# Full_PCB.net
KiCad netlist of a schematic drawn in EAGLE
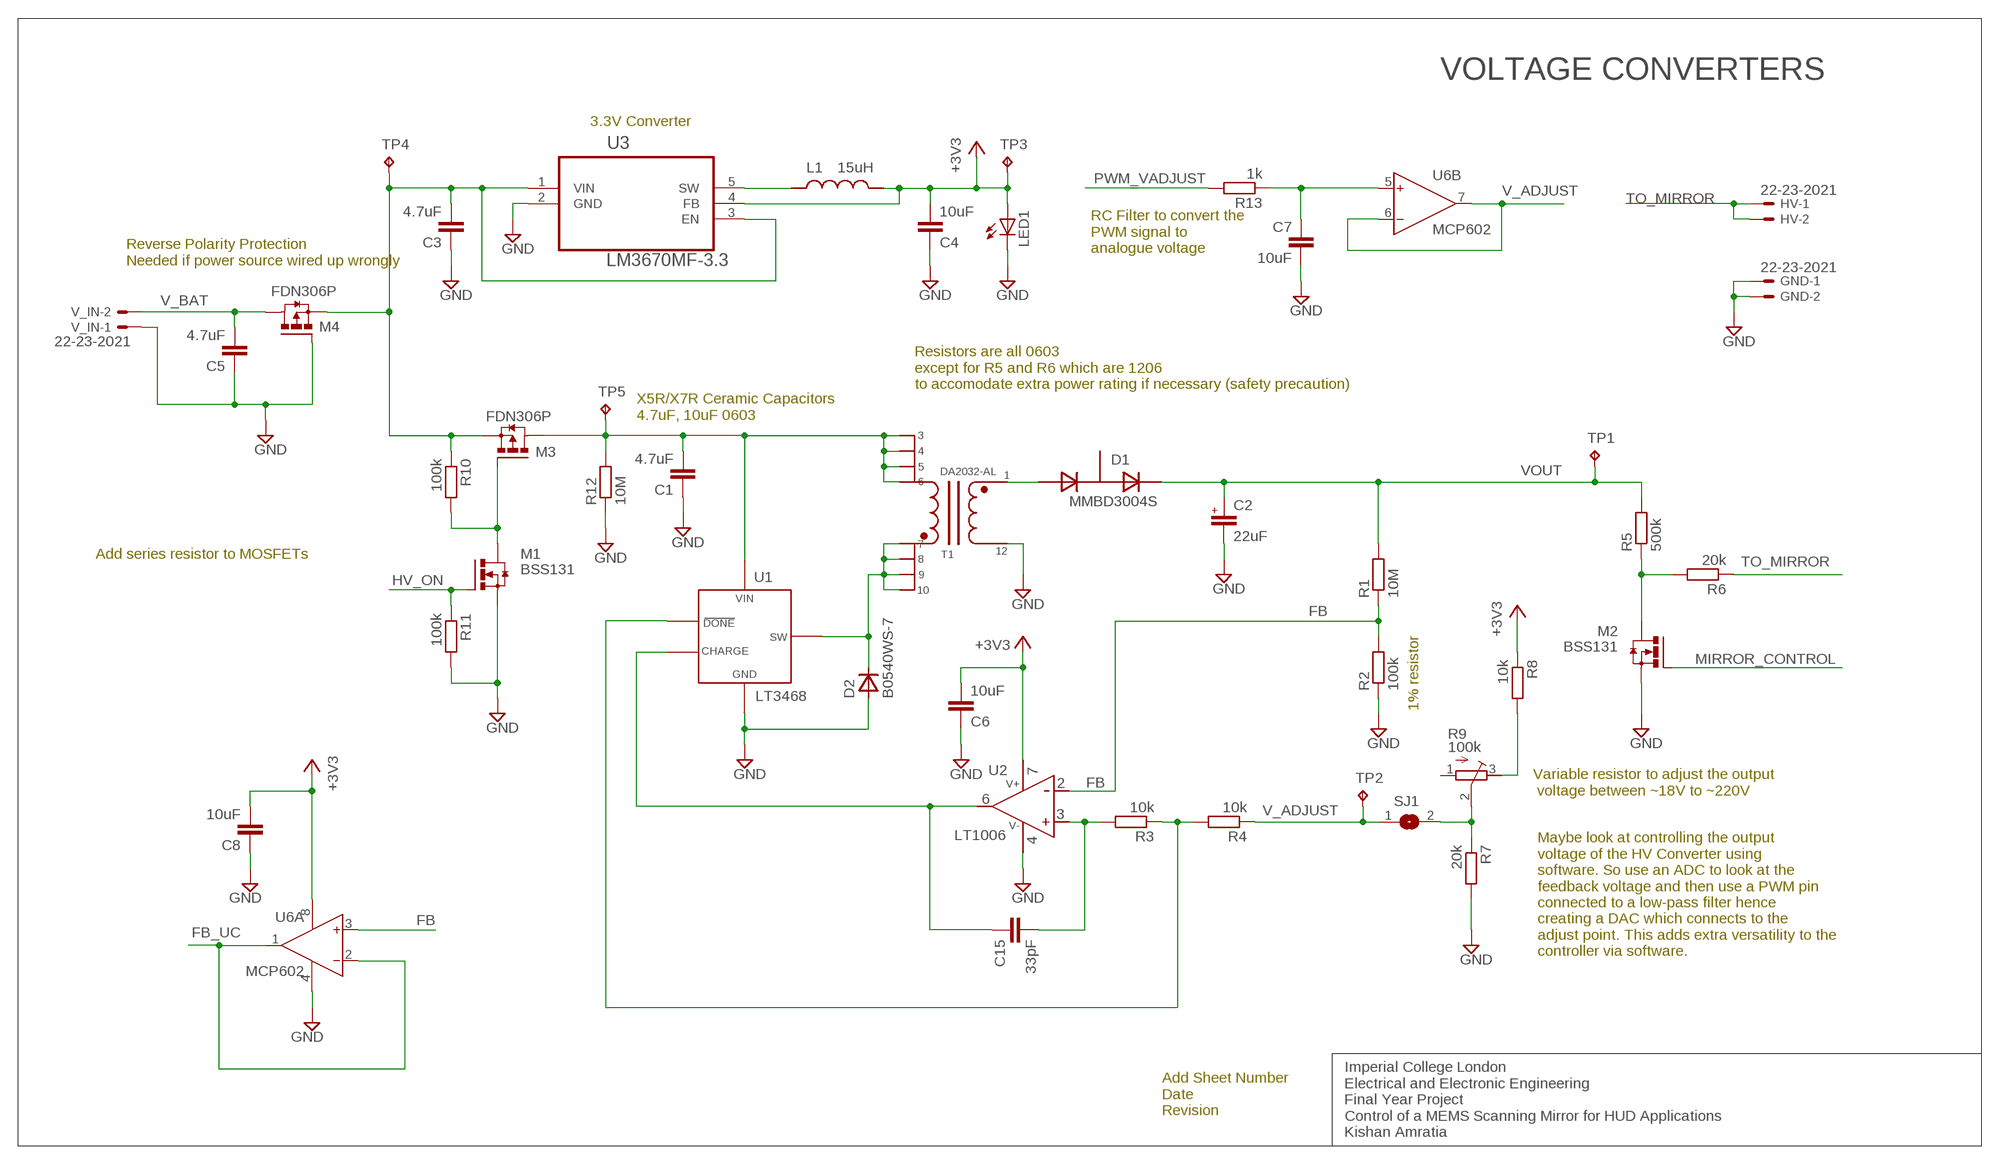
[diagram p0: schematic, sheet 1]
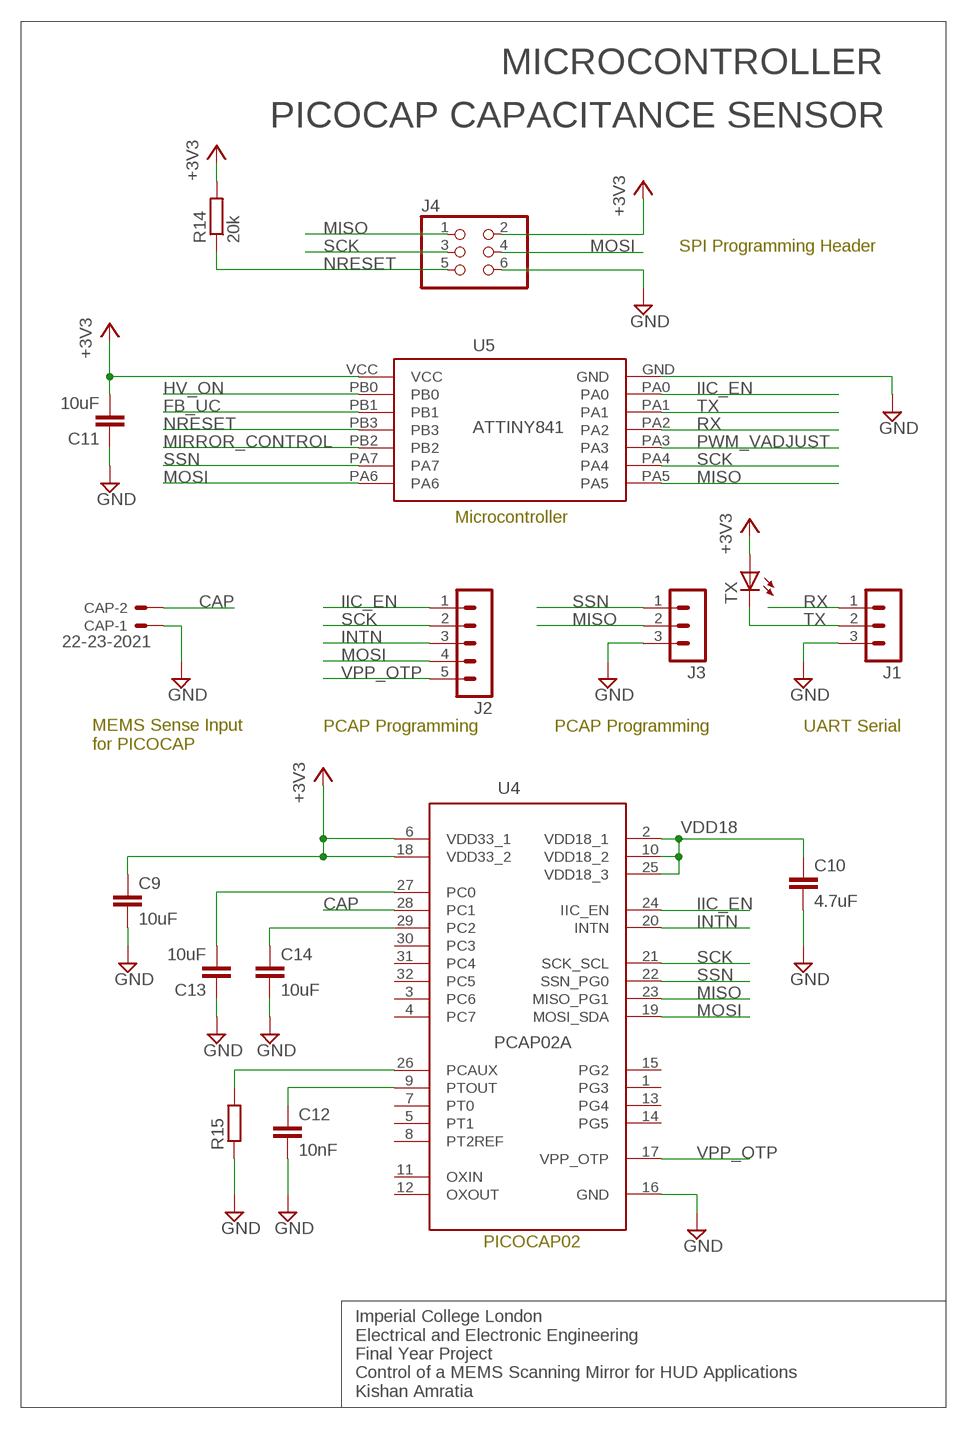
[diagram p1: schematic, sheet 2]

(export (version "E")
  (design (tool "Eeschema 10.0.6"))
  (components
    (comp (ref "C1")
      (value "4.7uF")
      (footprint "eagle-import:C0603K")
      (libsource (lib "eagle-import") (part "C-EUC0603K"))
    )
    (comp (ref "C2")
      (value "22uF")
      (footprint "eagle-import:5MM-RADIAL-LEAD")
      (libsource (lib "eagle-import") (part "EEUEE2E220"))
    )
    (comp (ref "C3")
      (value "4.7uF")
      (footprint "eagle-import:C0603K")
      (libsource (lib "eagle-import") (part "C-EUC0603K"))
    )
    (comp (ref "C4")
      (value "10uF")
      (footprint "eagle-import:C0603")
      (libsource (lib "eagle-import") (part "C-EUC0603"))
    )
    (comp (ref "C5")
      (value "4.7uF")
      (footprint "eagle-import:C0603K")
      (libsource (lib "eagle-import") (part "C-EUC0603K"))
    )
    (comp (ref "C6")
      (value "10uF")
      (footprint "eagle-import:C0603")
      (libsource (lib "eagle-import") (part "C-EUC0603"))
    )
    (comp (ref "C7")
      (value "10uF")
      (footprint "eagle-import:C0603")
      (libsource (lib "eagle-import") (part "C-EUC0603"))
    )
    (comp (ref "C8")
      (value "10uF")
      (footprint "eagle-import:C0603")
      (libsource (lib "eagle-import") (part "C-EUC0603"))
    )
    (comp (ref "C15")
      (value "33pF")
      (footprint "eagle-import:C0603")
      (libsource (lib "eagle-import") (part "C-EUC0603"))
    )
    (comp (ref "D1")
      (value "MMBD3004S")
      (footprint "eagle-import:SOT-23")
      (libsource (lib "eagle-import") (part "MMBD3004S"))
    )
    (comp (ref "D2")
      (value "B0540WS-7")
      (footprint "eagle-import:SOD-323")
      (libsource (lib "eagle-import") (part "B0540WS-7"))
    )
    (comp (ref "GND")
      (value "22-23-2021")
      (footprint "eagle-import:22-23-2021")
      (fields (field (name "MF") "MOLEX"))
      (libsource (lib "eagle-import") (part "22-23-2021"))
    )
    (comp (ref "HV")
      (value "22-23-2021")
      (footprint "eagle-import:22-23-2021")
      (fields (field (name "MF") "MOLEX"))
      (libsource (lib "eagle-import") (part "22-23-2021"))
    )
    (comp (ref "L1")
      (value "15uH")
      (footprint "eagle-import:IFSC1515AHER150M01")
      (libsource (lib "eagle-import") (part "IFSC1515AHER150M01"))
    )
    (comp (ref "LED1")
      (value "LEDCHIPLED_0603")
      (footprint "eagle-import:CHIPLED_0603")
      (libsource (lib "eagle-import") (part "LEDCHIPLED_0603"))
    )
    (comp (ref "M1")
      (value "BSS131")
      (footprint "eagle-import:SOT-23")
      (libsource (lib "eagle-import") (part "BSS131"))
    )
    (comp (ref "M2")
      (value "BSS131")
      (footprint "eagle-import:SOT-23")
      (libsource (lib "eagle-import") (part "BSS131"))
    )
    (comp (ref "M3")
      (value "FDN306P")
      (footprint "eagle-import:SSOT-3")
      (libsource (lib "eagle-import") (part "FDN306P"))
    )
    (comp (ref "M4")
      (value "FDN306P")
      (footprint "eagle-import:SSOT-3")
      (libsource (lib "eagle-import") (part "FDN306P"))
    )
    (comp (ref "R1")
      (value "10M")
      (footprint "eagle-import:R0603")
      (libsource (lib "eagle-import") (part "R-EU_R0603"))
    )
    (comp (ref "R2")
      (value "100k")
      (footprint "eagle-import:R0603")
      (libsource (lib "eagle-import") (part "R-EU_R0603"))
    )
    (comp (ref "R3")
      (value "10k")
      (footprint "eagle-import:R0603")
      (libsource (lib "eagle-import") (part "R-EU_R0603"))
    )
    (comp (ref "R4")
      (value "10k")
      (footprint "eagle-import:R0603")
      (libsource (lib "eagle-import") (part "R-EU_R0603"))
    )
    (comp (ref "R5")
      (value "500k")
      (footprint "eagle-import:R1206")
      (libsource (lib "eagle-import") (part "R-EU_R1206"))
    )
    (comp (ref "R6")
      (value "20k")
      (footprint "eagle-import:R1206")
      (libsource (lib "eagle-import") (part "R-EU_R1206"))
    )
    (comp (ref "R7")
      (value "20k")
      (footprint "eagle-import:R0603")
      (libsource (lib "eagle-import") (part "R-EU_R0603"))
    )
    (comp (ref "R8")
      (value "10k")
      (footprint "eagle-import:R0603")
      (libsource (lib "eagle-import") (part "R-EU_R0603"))
    )
    (comp (ref "R9")
      (value "100k")
      (footprint "eagle-import:TC33X-2-104E")
      (libsource (lib "eagle-import") (part "TC33X-2-104E"))
    )
    (comp (ref "R10")
      (value "100k")
      (footprint "eagle-import:R0603")
      (libsource (lib "eagle-import") (part "R-EU_R0603"))
    )
    (comp (ref "R11")
      (value "100k")
      (footprint "eagle-import:R0603")
      (libsource (lib "eagle-import") (part "R-EU_R0603"))
    )
    (comp (ref "R12")
      (value "10M")
      (footprint "eagle-import:R0603")
      (libsource (lib "eagle-import") (part "R-EU_R0603"))
    )
    (comp (ref "R13")
      (value "1k")
      (footprint "eagle-import:R0603")
      (libsource (lib "eagle-import") (part "R-EU_R0603"))
    )
    (comp (ref "SJ1") (value "SJ") (footprint "eagle-import:SJ") (libsource (lib "eagle-import") (part "SJ")))
    (comp (ref "T1")
      (value "DA2032-AL")
      (footprint "eagle-import:DA2032-AL")
      (libsource (lib "eagle-import") (part "DA2032-AL"))
    )
    (comp (ref "TP1")
      (value "TPB1,27")
      (footprint "eagle-import:B1,27")
      (libsource (lib "eagle-import") (part "TPB1,27"))
    )
    (comp (ref "TP2")
      (value "TPB1,27")
      (footprint "eagle-import:B1,27")
      (libsource (lib "eagle-import") (part "TPB1,27"))
    )
    (comp (ref "TP3")
      (value "TPB1,27")
      (footprint "eagle-import:B1,27")
      (libsource (lib "eagle-import") (part "TPB1,27"))
    )
    (comp (ref "TP4")
      (value "TPB1,27")
      (footprint "eagle-import:B1,27")
      (libsource (lib "eagle-import") (part "TPB1,27"))
    )
    (comp (ref "TP5")
      (value "TPB1,27")
      (footprint "eagle-import:B1,27")
      (libsource (lib "eagle-import") (part "TPB1,27"))
    )
    (comp (ref "U1")
      (value "LT3468")
      (footprint "eagle-import:TSOT-23")
      (libsource (lib "eagle-import") (part "LT3468"))
    )
    (comp (ref "U2")
      (value "LT1006")
      (footprint "eagle-import:SOIC127P600X175-8N")
      (libsource (lib "eagle-import") (part "LT1006"))
    )
    (comp (ref "U3")
      (value "LM3670MF-3.3")
      (footprint "eagle-import:SOT95P284X122-5N")
      (libsource (lib "eagle-import") (part "LM3670MF-3.3"))
    )
    (comp (ref "U6")
      (value "MCP602")
      (footprint "eagle-import:SOIC127P600X175-8N")
      (libsource (lib "eagle-import") (part "MCP602"))
    )
    (comp (ref "V_IN")
      (value "22-23-2021")
      (footprint "eagle-import:22-23-2021")
      (fields (field (name "MF") "MOLEX"))
      (libsource (lib "eagle-import") (part "22-23-2021"))
    )
    (comp (ref "C9")
      (value "10uF")
      (footprint "eagle-import:C0603K")
      (libsource (lib "eagle-import") (part "C-EUC0603K"))
    )
    (comp (ref "C10")
      (value "4.7uF")
      (footprint "eagle-import:C0603K")
      (libsource (lib "eagle-import") (part "C-EUC0603K"))
    )
    (comp (ref "C11")
      (value "10uF")
      (footprint "eagle-import:C0603K")
      (libsource (lib "eagle-import") (part "C-EUC0603K"))
    )
    (comp (ref "C12")
      (value "10nF")
      (footprint "eagle-import:C0603K")
      (libsource (lib "eagle-import") (part "C-EUC0603K"))
    )
    (comp (ref "C13")
      (value "10uF")
      (footprint "eagle-import:C0603K")
      (libsource (lib "eagle-import") (part "C-EUC0603K"))
    )
    (comp (ref "C14")
      (value "10uF")
      (footprint "eagle-import:C0603K")
      (libsource (lib "eagle-import") (part "C-EUC0603K"))
    )
    (comp (ref "CAP")
      (value "22-23-2021")
      (footprint "eagle-import:22-23-2021")
      (fields (field (name "MF") "MOLEX"))
      (libsource (lib "eagle-import") (part "22-23-2021"))
    )
    (comp (ref "J1")
      (value "MA03-1")
      (footprint "eagle-import:MA03-1")
      (libsource (lib "eagle-import") (part "MA03-1"))
    )
    (comp (ref "J2")
      (value "MA05-1")
      (footprint "eagle-import:MA05-1")
      (libsource (lib "eagle-import") (part "MA05-1"))
    )
    (comp (ref "J3")
      (value "MA03-1")
      (footprint "eagle-import:MA03-1")
      (libsource (lib "eagle-import") (part "MA03-1"))
    )
    (comp (ref "J4")
      (value "PINHD-2X3")
      (footprint "eagle-import:2X03")
      (libsource (lib "eagle-import") (part "PINHD-2X3"))
    )
    (comp (ref "R14")
      (value "20k")
      (footprint "eagle-import:R0603")
      (libsource (lib "eagle-import") (part "R-EU_R0603"))
    )
    (comp (ref "R15")
      (value "R-EU_R0603")
      (footprint "eagle-import:R0603")
      (libsource (lib "eagle-import") (part "R-EU_R0603"))
    )
    (comp (ref "TX")
      (value "LEDCHIPLED_0603")
      (footprint "eagle-import:CHIPLED_0603")
      (libsource (lib "eagle-import") (part "LEDCHIPLED_0603"))
    )
    (comp (ref "U4")
      (value "PCAP02A")
      (footprint "eagle-import:QFN32")
      (libsource (lib "eagle-import") (part "PCAP02A"))
    )
    (comp (ref "U5")
      (value "ATTINY841")
      (footprint "eagle-import:SOIC-14")
      (libsource (lib "eagle-import") (part "ATTINY841"))
    )
  )
  (nets
    (net (code "1") (name "+3V3") (class "Default")
      (node (ref "C11") (pin "2") (pinfunction "2_2") (pintype "passive"))
      (node (ref "C4") (pin "2") (pinfunction "2_2") (pintype "passive"))
      (node (ref "C6") (pin "2") (pinfunction "2_2") (pintype "passive"))
      (node (ref "C8") (pin "2") (pinfunction "2_2") (pintype "passive"))
      (node (ref "C9") (pin "1") (pinfunction "1_1") (pintype "passive"))
      (node (ref "J4") (pin "2") (pinfunction "2_2") (pintype "passive"))
      (node (ref "L1") (pin "2") (pinfunction "2_2") (pintype "bidirectional"))
      (node (ref "LED1") (pin "A") (pinfunction "A_A") (pintype "passive"))
      (node (ref "R14") (pin "2") (pinfunction "2_2") (pintype "passive"))
      (node (ref "R8") (pin "1") (pinfunction "1_1") (pintype "passive"))
      (node (ref "TP3") (pin "TP") (pinfunction "TP_TP") (pintype "input"))
      (node (ref "TX") (pin "A") (pinfunction "A_A") (pintype "passive"))
      (node (ref "U2") (pin "7") (pinfunction "7_7") (pintype "bidirectional"))
      (node (ref "U3") (pin "4") (pinfunction "FB_4") (pintype "passive"))
      (node (ref "U4") (pin "18") (pinfunction "VDD33_2_18") (pintype "power_in"))
      (node (ref "U4") (pin "6") (pinfunction "VDD33_1_6") (pintype "power_in"))
      (node (ref "U5") (pin "VCC") (pinfunction "VCC_VCC") (pintype "bidirectional"))
      (node (ref "U6") (pin "8") (pinfunction "V+_8") (pintype "power_in"))
    )
    (net (code "2") (name "CAP") (class "Default")
      (node (ref "CAP") (pin "2") (pinfunction "S_2") (pintype "passive"))
      (node (ref "U4") (pin "28") (pinfunction "PC1_28") (pintype "bidirectional"))
    )
    (net (code "3") (name "FB") (class "Default")
      (node (ref "R1") (pin "1") (pinfunction "1_1") (pintype "passive"))
      (node (ref "R2") (pin "2") (pinfunction "2_2") (pintype "passive"))
      (node (ref "U2") (pin "2") (pinfunction "2_2") (pintype "bidirectional"))
      (node (ref "U6") (pin "3") (pinfunction "IN+_3") (pintype "input"))
    )
    (net (code "4") (name "FB_UC") (class "Default")
      (node (ref "U5") (pin "PB1") (pinfunction "PB1_PB1") (pintype "bidirectional"))
      (node (ref "U6") (pin "1") (pinfunction "OUT_1") (pintype "output"))
      (node (ref "U6") (pin "2") (pinfunction "IN-_2") (pintype "input"))
    )
    (net (code "5") (name "GND") (class "Default")
      (node (ref "C1") (pin "1") (pinfunction "1_1") (pintype "passive"))
      (node (ref "C10") (pin "2") (pinfunction "2_2") (pintype "passive"))
      (node (ref "C11") (pin "1") (pinfunction "1_1") (pintype "passive"))
      (node (ref "C12") (pin "2") (pinfunction "2_2") (pintype "passive"))
      (node (ref "C13") (pin "1") (pinfunction "1_1") (pintype "passive"))
      (node (ref "C14") (pin "2") (pinfunction "2_2") (pintype "passive"))
      (node (ref "C2") (pin "2") (pinfunction "2_2") (pintype "passive"))
      (node (ref "C3") (pin "1") (pinfunction "1_1") (pintype "passive"))
      (node (ref "C4") (pin "1") (pinfunction "1_1") (pintype "passive"))
      (node (ref "C5") (pin "1") (pinfunction "1_1") (pintype "passive"))
      (node (ref "C6") (pin "1") (pinfunction "1_1") (pintype "passive"))
      (node (ref "C7") (pin "2") (pinfunction "2_2") (pintype "passive"))
      (node (ref "C8") (pin "1") (pinfunction "1_1") (pintype "passive"))
      (node (ref "C9") (pin "2") (pinfunction "2_2") (pintype "passive"))
      (node (ref "CAP") (pin "1") (pinfunction "S_1") (pintype "passive"))
      (node (ref "D2") (pin "A") (pinfunction "A_A") (pintype "bidirectional"))
      (node (ref "GND") (pin "1") (pinfunction "S_1") (pintype "passive"))
      (node (ref "GND") (pin "2") (pinfunction "S_2") (pintype "passive"))
      (node (ref "J1") (pin "3") (pinfunction "3_3") (pintype "passive"))
      (node (ref "J3") (pin "3") (pinfunction "3_3") (pintype "passive"))
      (node (ref "J4") (pin "6") (pinfunction "6_6") (pintype "passive"))
      (node (ref "LED1") (pin "C") (pinfunction "C_C") (pintype "passive"))
      (node (ref "M1") (pin "K") (pinfunction "S_K") (pintype "passive"))
      (node (ref "M2") (pin "K") (pinfunction "S_K") (pintype "passive"))
      (node (ref "M4") (pin "1") (pinfunction "G_1") (pintype "passive"))
      (node (ref "R11") (pin "2") (pinfunction "2_2") (pintype "passive"))
      (node (ref "R12") (pin "1") (pinfunction "1_1") (pintype "passive"))
      (node (ref "R15") (pin "1") (pinfunction "1_1") (pintype "passive"))
      (node (ref "R2") (pin "1") (pinfunction "1_1") (pintype "passive"))
      (node (ref "R7") (pin "2") (pinfunction "2_2") (pintype "passive"))
      (node (ref "T1") (pin "12") (pinfunction "12_12") (pintype "bidirectional"))
      (node (ref "U1") (pin "2") (pinfunction "2_2") (pintype "output"))
      (node (ref "U2") (pin "4") (pinfunction "4_4") (pintype "bidirectional"))
      (node (ref "U3") (pin "2") (pinfunction "GND_2") (pintype "passive"))
      (node (ref "U4") (pin "16") (pinfunction "GND_16") (pintype "power_in"))
      (node (ref "U5") (pin "GND") (pinfunction "GND_GND") (pintype "bidirectional"))
      (node (ref "U6") (pin "4") (pinfunction "V-_4") (pintype "power_in"))
      (node (ref "V_IN") (pin "1") (pinfunction "S_1") (pintype "passive"))
    )
    (net (code "6") (name "HV_ON") (class "Default")
      (node (ref "M1") (pin "A") (pinfunction "G_A") (pintype "passive"))
      (node (ref "R11") (pin "1") (pinfunction "1_1") (pintype "passive"))
      (node (ref "U5") (pin "PB0") (pinfunction "PB0_PB0") (pintype "bidirectional"))
    )
    (net (code "7") (name "IIC_EN") (class "Default")
      (node (ref "J2") (pin "1") (pinfunction "1_1") (pintype "passive"))
      (node (ref "U4") (pin "24") (pinfunction "IIC_EN_24") (pintype "input"))
      (node (ref "U5") (pin "PA0") (pinfunction "PA0_PA0") (pintype "bidirectional"))
    )
    (net (code "8") (name "INTN") (class "Default")
      (node (ref "J2") (pin "3") (pinfunction "3_3") (pintype "passive"))
      (node (ref "U4") (pin "20") (pinfunction "INTN_20") (pintype "output"))
    )
    (net (code "9") (name "MIRROR_CONTROL") (class "Default")
      (node (ref "M2") (pin "A") (pinfunction "G_A") (pintype "passive"))
      (node (ref "U5") (pin "PB2") (pinfunction "PB2_PB2") (pintype "bidirectional"))
    )
    (net (code "10") (name "MISO") (class "Default")
      (node (ref "J3") (pin "2") (pinfunction "2_2") (pintype "passive"))
      (node (ref "J4") (pin "1") (pinfunction "1_1") (pintype "passive"))
      (node (ref "U4") (pin "23") (pinfunction "MISO_PG1_23") (pintype "bidirectional"))
      (node (ref "U5") (pin "PA5") (pinfunction "PA5_PA5") (pintype "bidirectional"))
    )
    (net (code "11") (name "MOSI") (class "Default")
      (node (ref "J2") (pin "4") (pinfunction "4_4") (pintype "passive"))
      (node (ref "J4") (pin "4") (pinfunction "4_4") (pintype "passive"))
      (node (ref "U4") (pin "19") (pinfunction "MOSI_SDA_19") (pintype "bidirectional"))
      (node (ref "U5") (pin "PA6") (pinfunction "PA6_PA6") (pintype "bidirectional"))
    )
    (net (code "12") (name "NRESET") (class "Default")
      (node (ref "J4") (pin "5") (pinfunction "5_5") (pintype "passive"))
      (node (ref "R14") (pin "1") (pinfunction "1_1") (pintype "passive"))
      (node (ref "U5") (pin "PB3") (pinfunction "PB3_PB3") (pintype "bidirectional"))
    )
    (net (code "13") (name "Net-(C15-Pad1)") (class "Default")
      (node (ref "C15") (pin "1") (pinfunction "1_1") (pintype "passive"))
      (node (ref "U1") (pin "4") (pinfunction "4_4") (pintype "output"))
      (node (ref "U2") (pin "6") (pinfunction "6_6") (pintype "bidirectional"))
    )
    (net (code "14") (name "Net-(C15-Pad2)") (class "Default")
      (node (ref "C15") (pin "2") (pinfunction "2_2") (pintype "passive"))
      (node (ref "R3") (pin "2") (pinfunction "2_2") (pintype "passive"))
      (node (ref "U2") (pin "3") (pinfunction "3_3") (pintype "bidirectional"))
    )
    (net (code "15") (name "Net-(D1-PadA)") (class "Default")
      (node (ref "D1") (pin "A") (pinfunction "A_A") (pintype "bidirectional"))
      (node (ref "T1") (pin "1") (pinfunction "1_1") (pintype "bidirectional"))
    )
    (net (code "16") (name "Net-(D2-PadK)") (class "Default")
      (node (ref "D2") (pin "K") (pinfunction "K_K") (pintype "bidirectional"))
      (node (ref "T1") (pin "10") (pinfunction "10_10") (pintype "bidirectional"))
      (node (ref "T1") (pin "7") (pinfunction "7_7") (pintype "bidirectional"))
      (node (ref "T1") (pin "8") (pinfunction "8_8") (pintype "bidirectional"))
      (node (ref "T1") (pin "9") (pinfunction "9_9") (pintype "bidirectional"))
      (node (ref "U1") (pin "1") (pinfunction "1_1") (pintype "output"))
    )
    (net (code "17") (name "Net-(M1-D)") (class "Default")
      (node (ref "M1") (pin "K1A2") (pinfunction "D_K1A2") (pintype "passive"))
      (node (ref "M3") (pin "1") (pinfunction "G_1") (pintype "passive"))
      (node (ref "R10") (pin "2") (pinfunction "2_2") (pintype "passive"))
    )
    (net (code "18") (name "Net-(M2-D)") (class "Default")
      (node (ref "M2") (pin "K1A2") (pinfunction "D_K1A2") (pintype "passive"))
      (node (ref "R5") (pin "1") (pinfunction "1_1") (pintype "passive"))
      (node (ref "R6") (pin "2") (pinfunction "2_2") (pintype "passive"))
    )
    (net (code "19") (name "Net-(M3-D)") (class "Default")
      (node (ref "C1") (pin "2") (pinfunction "2_2") (pintype "passive"))
      (node (ref "M3") (pin "3") (pinfunction "D_3") (pintype "passive"))
      (node (ref "R12") (pin "2") (pinfunction "2_2") (pintype "passive"))
      (node (ref "T1") (pin "3") (pinfunction "3_3") (pintype "bidirectional"))
      (node (ref "T1") (pin "4") (pinfunction "4_4") (pintype "bidirectional"))
      (node (ref "T1") (pin "5") (pinfunction "5_5") (pintype "bidirectional"))
      (node (ref "T1") (pin "6") (pinfunction "6_6") (pintype "bidirectional"))
      (node (ref "TP5") (pin "TP") (pinfunction "TP_TP") (pintype "input"))
      (node (ref "U1") (pin "5") (pinfunction "5_5") (pintype "output"))
    )
    (net (code "20") (name "Net-(M3-S)") (class "Default")
      (node (ref "C3") (pin "2") (pinfunction "2_2") (pintype "passive"))
      (node (ref "M3") (pin "2") (pinfunction "S_2") (pintype "passive"))
      (node (ref "M4") (pin "2") (pinfunction "S_2") (pintype "passive"))
      (node (ref "R10") (pin "1") (pinfunction "1_1") (pintype "passive"))
      (node (ref "TP4") (pin "TP") (pinfunction "TP_TP") (pintype "input"))
      (node (ref "U3") (pin "1") (pinfunction "VIN_1") (pintype "input"))
      (node (ref "U3") (pin "3") (pinfunction "EN_3") (pintype "passive"))
    )
    (net (code "21") (name "Net-(R3-Pad1)") (class "Default")
      (node (ref "R3") (pin "1") (pinfunction "1_1") (pintype "passive"))
      (node (ref "R4") (pin "2") (pinfunction "2_2") (pintype "passive"))
      (node (ref "U1") (pin "3") (pinfunction "3_3") (pintype "output"))
    )
    (net (code "22") (name "Net-(R7-Pad1)") (class "Default")
      (node (ref "R7") (pin "1") (pinfunction "1_1") (pintype "passive"))
      (node (ref "R9") (pin "2") (pinfunction "2_2") (pintype "passive"))
      (node (ref "SJ1") (pin "2") (pinfunction "2_2") (pintype "passive"))
    )
    (net (code "23") (name "Net-(R8-Pad2)") (class "Default")
      (node (ref "R8") (pin "2") (pinfunction "2_2") (pintype "passive"))
      (node (ref "R9") (pin "3") (pinfunction "3_3") (pintype "passive"))
    )
    (net (code "24") (name "Net-(U3-SW)") (class "Default")
      (node (ref "L1") (pin "1") (pinfunction "1_1") (pintype "bidirectional"))
      (node (ref "U3") (pin "5") (pinfunction "SW_5") (pintype "output"))
    )
    (net (code "25") (name "Net-(U4-PC0)") (class "Default")
      (node (ref "C13") (pin "2") (pinfunction "2_2") (pintype "passive"))
      (node (ref "U4") (pin "27") (pinfunction "PC0_27") (pintype "bidirectional"))
    )
    (net (code "26") (name "Net-(U4-PC2)") (class "Default")
      (node (ref "C14") (pin "1") (pinfunction "1_1") (pintype "passive"))
      (node (ref "U4") (pin "29") (pinfunction "PC2_29") (pintype "bidirectional"))
    )
    (net (code "27") (name "Net-(U4-PCAUX)") (class "Default")
      (node (ref "R15") (pin "2") (pinfunction "2_2") (pintype "passive"))
      (node (ref "U4") (pin "26") (pinfunction "PCAUX_26") (pintype "bidirectional"))
    )
    (net (code "28") (name "Net-(U4-PTOUT)") (class "Default")
      (node (ref "C12") (pin "1") (pinfunction "1_1") (pintype "passive"))
      (node (ref "U4") (pin "9") (pinfunction "PTOUT_9") (pintype "bidirectional"))
    )
    (net (code "29") (name "Net-(U6B-IN+)") (class "Default")
      (node (ref "C7") (pin "1") (pinfunction "1_1") (pintype "passive"))
      (node (ref "R13") (pin "1") (pinfunction "1_1") (pintype "passive"))
      (node (ref "U6") (pin "5") (pinfunction "IN+_5") (pintype "input"))
    )
    (net (code "30") (name "PWM_VADJUST") (class "Default")
      (node (ref "R13") (pin "2") (pinfunction "2_2") (pintype "passive"))
      (node (ref "U5") (pin "PA3") (pinfunction "PA3_PA3") (pintype "bidirectional"))
    )
    (net (code "31") (name "RX") (class "Default")
      (node (ref "J1") (pin "1") (pinfunction "1_1") (pintype "passive"))
      (node (ref "U5") (pin "PA2") (pinfunction "PA2_PA2") (pintype "bidirectional"))
    )
    (net (code "32") (name "SCK") (class "Default")
      (node (ref "J2") (pin "2") (pinfunction "2_2") (pintype "passive"))
      (node (ref "J4") (pin "3") (pinfunction "3_3") (pintype "passive"))
      (node (ref "U4") (pin "21") (pinfunction "SCK_SCL_21") (pintype "bidirectional"))
      (node (ref "U5") (pin "PA4") (pinfunction "PA4_PA4") (pintype "bidirectional"))
    )
    (net (code "33") (name "SSN") (class "Default")
      (node (ref "J3") (pin "1") (pinfunction "1_1") (pintype "passive"))
      (node (ref "U4") (pin "22") (pinfunction "SSN_PG0_22") (pintype "bidirectional"))
      (node (ref "U5") (pin "PA7") (pinfunction "PA7_PA7") (pintype "bidirectional"))
    )
    (net (code "34") (name "TO_MIRROR") (class "Default")
      (node (ref "HV") (pin "1") (pinfunction "S_1") (pintype "passive"))
      (node (ref "HV") (pin "2") (pinfunction "S_2") (pintype "passive"))
      (node (ref "R6") (pin "1") (pinfunction "1_1") (pintype "passive"))
    )
    (net (code "35") (name "TX") (class "Default")
      (node (ref "J1") (pin "2") (pinfunction "2_2") (pintype "passive"))
      (node (ref "TX") (pin "C") (pinfunction "C_C") (pintype "passive"))
      (node (ref "U5") (pin "PA1") (pinfunction "PA1_PA1") (pintype "bidirectional"))
    )
    (net (code "36") (name "VDD18") (class "Default")
      (node (ref "C10") (pin "1") (pinfunction "1_1") (pintype "passive"))
      (node (ref "U4") (pin "10") (pinfunction "VDD18_2_10") (pintype "bidirectional"))
      (node (ref "U4") (pin "2") (pinfunction "VDD18_1_2") (pintype "bidirectional"))
      (node (ref "U4") (pin "25") (pinfunction "VDD18_3_25") (pintype "bidirectional"))
    )
    (net (code "37") (name "VOUT") (class "Default")
      (node (ref "C2") (pin "1+") (pinfunction "1+_1+") (pintype "passive"))
      (node (ref "D1") (pin "K") (pinfunction "K_K") (pintype "bidirectional"))
      (node (ref "R1") (pin "2") (pinfunction "2_2") (pintype "passive"))
      (node (ref "R5") (pin "2") (pinfunction "2_2") (pintype "passive"))
      (node (ref "TP1") (pin "TP") (pinfunction "TP_TP") (pintype "input"))
    )
    (net (code "38") (name "VPP_OTP") (class "Default")
      (node (ref "J2") (pin "5") (pinfunction "5_5") (pintype "passive"))
      (node (ref "U4") (pin "17") (pinfunction "VPP_OTP_17") (pintype "bidirectional"))
    )
    (net (code "39") (name "V_ADJUST") (class "Default")
      (node (ref "R4") (pin "1") (pinfunction "1_1") (pintype "passive"))
      (node (ref "SJ1") (pin "1") (pinfunction "1_1") (pintype "passive"))
      (node (ref "TP2") (pin "TP") (pinfunction "TP_TP") (pintype "input"))
      (node (ref "U6") (pin "6") (pinfunction "IN-_6") (pintype "input"))
      (node (ref "U6") (pin "7") (pinfunction "OUT_7") (pintype "output"))
    )
    (net (code "40") (name "V_BAT") (class "Default")
      (node (ref "C5") (pin "2") (pinfunction "2_2") (pintype "passive"))
      (node (ref "M4") (pin "3") (pinfunction "D_3") (pintype "passive"))
      (node (ref "V_IN") (pin "2") (pinfunction "S_2") (pintype "passive"))
    )
    (net (code "41") (name "unconnected-(D1-PadK1A2)") (class "Default")
      (node (ref "D1") (pin "K1A2") (pinfunction "K1A2_K1A2") (pintype "bidirectional"))
    )
    (net (code "42") (name "unconnected-(R9-Pad1)") (class "Default")
      (node (ref "R9") (pin "1") (pinfunction "1_1") (pintype "passive"))
    )
    (net (code "43") (name "unconnected-(U4-OXIN-Pad11)") (class "Default")
      (node (ref "U4") (pin "11") (pinfunction "OXIN_11") (pintype "bidirectional"))
    )
    (net (code "44") (name "unconnected-(U4-OXOUT-Pad12)") (class "Default")
      (node (ref "U4") (pin "12") (pinfunction "OXOUT_12") (pintype "bidirectional"))
    )
    (net (code "45") (name "unconnected-(U4-PC3-Pad30)") (class "Default")
      (node (ref "U4") (pin "30") (pinfunction "PC3_30") (pintype "bidirectional"))
    )
    (net (code "46") (name "unconnected-(U4-PC4-Pad31)") (class "Default")
      (node (ref "U4") (pin "31") (pinfunction "PC4_31") (pintype "bidirectional"))
    )
    (net (code "47") (name "unconnected-(U4-PC5-Pad32)") (class "Default")
      (node (ref "U4") (pin "32") (pinfunction "PC5_32") (pintype "bidirectional"))
    )
    (net (code "48") (name "unconnected-(U4-PC6-Pad3)") (class "Default")
      (node (ref "U4") (pin "3") (pinfunction "PC6_3") (pintype "bidirectional"))
    )
    (net (code "49") (name "unconnected-(U4-PC7-Pad4)") (class "Default")
      (node (ref "U4") (pin "4") (pinfunction "PC7_4") (pintype "bidirectional"))
    )
    (net (code "50") (name "unconnected-(U4-PG2-Pad15)") (class "Default")
      (node (ref "U4") (pin "15") (pinfunction "PG2_15") (pintype "bidirectional"))
    )
    (net (code "51") (name "unconnected-(U4-PG3-Pad1)") (class "Default")
      (node (ref "U4") (pin "1") (pinfunction "PG3_1") (pintype "bidirectional"))
    )
    (net (code "52") (name "unconnected-(U4-PG4-Pad13)") (class "Default")
      (node (ref "U4") (pin "13") (pinfunction "PG4_13") (pintype "output"))
    )
    (net (code "53") (name "unconnected-(U4-PG5-Pad14)") (class "Default")
      (node (ref "U4") (pin "14") (pinfunction "PG5_14") (pintype "output"))
    )
    (net (code "54") (name "unconnected-(U4-PT0-Pad7)") (class "Default")
      (node (ref "U4") (pin "7") (pinfunction "PT0_7") (pintype "bidirectional"))
    )
    (net (code "55") (name "unconnected-(U4-PT1-Pad5)") (class "Default")
      (node (ref "U4") (pin "5") (pinfunction "PT1_5") (pintype "bidirectional"))
    )
    (net (code "56") (name "unconnected-(U4-PT2REF-Pad8)") (class "Default")
      (node (ref "U4") (pin "8") (pinfunction "PT2REF_8") (pintype "bidirectional"))
    )
  )
)
